# GrovePi__2_2.net
KiCad netlist of a schematic drawn in EAGLE
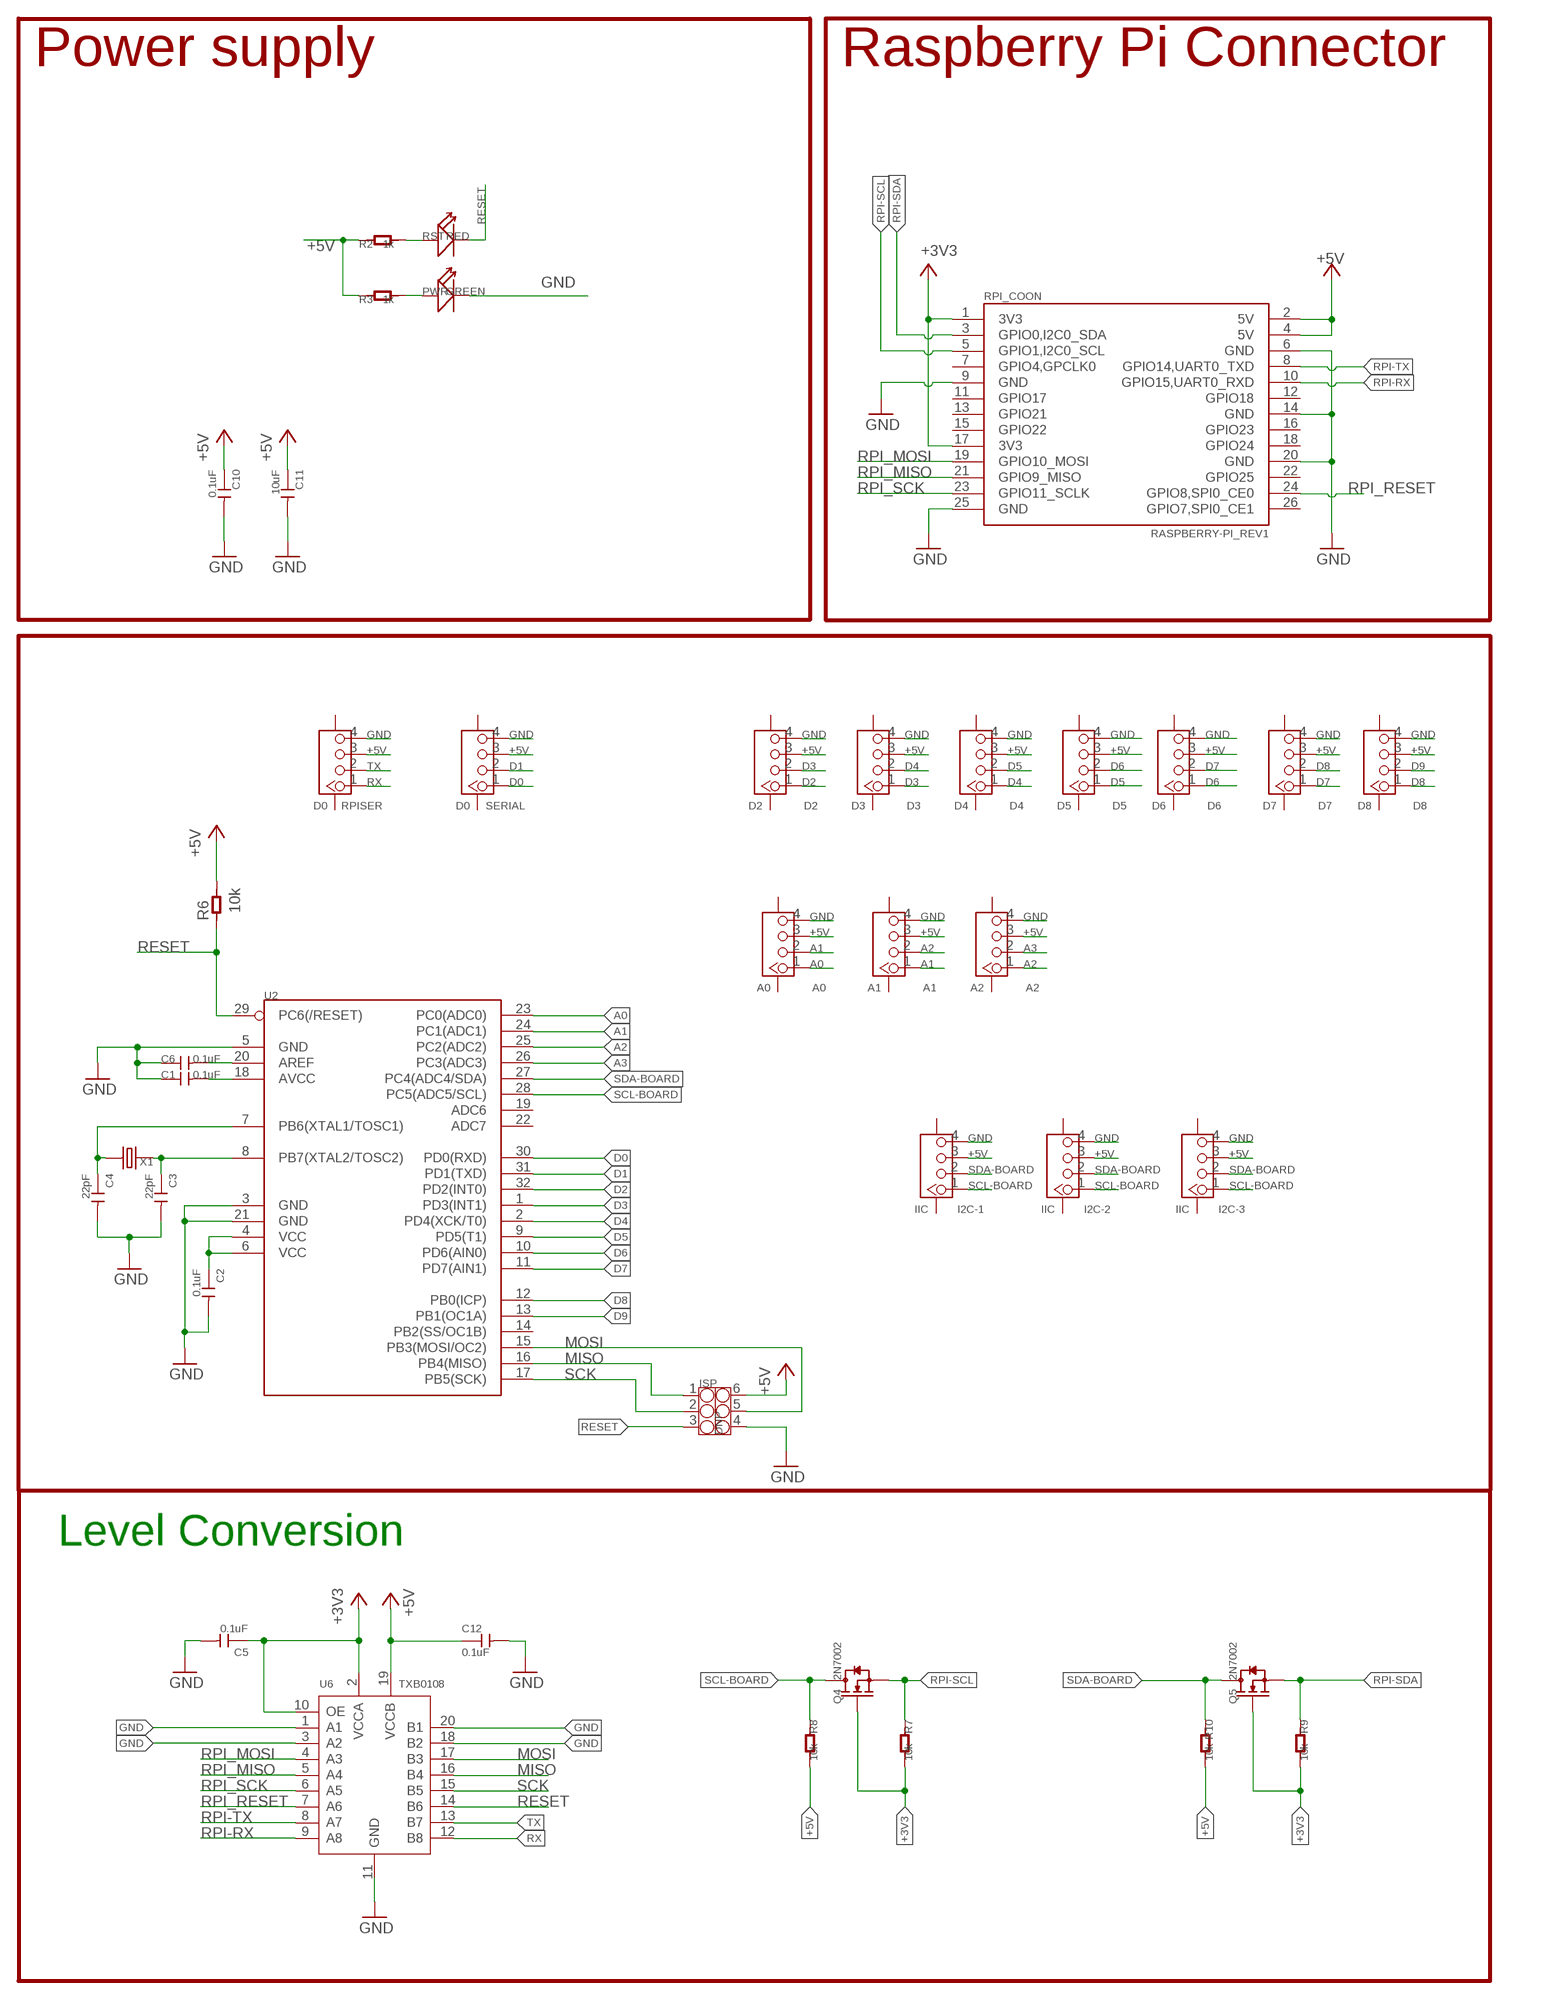
[diagram p0: schematic, sheet 1]

(export (version "E")
  (design (tool "Eeschema 10.0.6"))
  (components
    (comp (ref "A0")
      (value "A0")
      (footprint "eagle-import:4P-SMD-2.0-90D")
      (libsource (lib "eagle-import") (part "GROVE-CONNECTOR-SMD'90D'"))
    )
    (comp (ref "A1")
      (value "A1")
      (footprint "eagle-import:4P-SMD-2.0-90D")
      (libsource (lib "eagle-import") (part "GROVE-CONNECTOR-SMD'90D'"))
    )
    (comp (ref "A2")
      (value "A2")
      (footprint "eagle-import:4P-SMD-2.0-90D")
      (libsource (lib "eagle-import") (part "GROVE-CONNECTOR-SMD'90D'"))
    )
    (comp (ref "C1")
      (value "0.1uF")
      (footprint "eagle-import:C0603")
      (libsource (lib "eagle-import") (part "CAP-0603"))
    )
    (comp (ref "C2")
      (value "0.1uF")
      (footprint "eagle-import:C0603")
      (libsource (lib "eagle-import") (part "CAP-0603"))
    )
    (comp (ref "C3")
      (value "22pF")
      (footprint "eagle-import:C0603")
      (libsource (lib "eagle-import") (part "CAP-0603"))
    )
    (comp (ref "C4")
      (value "22pF")
      (footprint "eagle-import:C0603")
      (libsource (lib "eagle-import") (part "CAP-0603"))
    )
    (comp (ref "C5")
      (value "0.1uF")
      (footprint "eagle-import:C0603")
      (libsource (lib "eagle-import") (part "CAP-0603"))
    )
    (comp (ref "C6")
      (value "0.1uF")
      (footprint "eagle-import:C0603")
      (libsource (lib "eagle-import") (part "CAP-0603"))
    )
    (comp (ref "C10")
      (value "0.1uF")
      (footprint "eagle-import:C0603")
      (libsource (lib "eagle-import") (part "CAP-0603"))
    )
    (comp (ref "C11")
      (value "10uF")
      (footprint "eagle-import:C0805")
      (libsource (lib "eagle-import") (part "CAP-0805"))
    )
    (comp (ref "C12")
      (value "0.1uF")
      (footprint "eagle-import:C0603")
      (libsource (lib "eagle-import") (part "CAP-0603"))
    )
    (comp (ref "D2")
      (value "D2")
      (footprint "eagle-import:4P-SMD-2.0-90D")
      (libsource (lib "eagle-import") (part "GROVE-CONNECTOR-SMD'90D'"))
    )
    (comp (ref "D3")
      (value "D3")
      (footprint "eagle-import:4P-SMD-2.0-90D")
      (libsource (lib "eagle-import") (part "GROVE-CONNECTOR-SMD'90D'"))
    )
    (comp (ref "D4")
      (value "D4")
      (footprint "eagle-import:4P-SMD-2.0-90D")
      (libsource (lib "eagle-import") (part "GROVE-CONNECTOR-SMD'90D'"))
    )
    (comp (ref "D5")
      (value "D5")
      (footprint "eagle-import:4P-SMD-2.0")
      (libsource (lib "eagle-import") (part "GROVE-CONNECTOR-SMD'DD'"))
    )
    (comp (ref "D6")
      (value "D6")
      (footprint "eagle-import:4P-SMD-2.0")
      (libsource (lib "eagle-import") (part "GROVE-CONNECTOR-SMD'DD'"))
    )
    (comp (ref "D7")
      (value "D7")
      (footprint "eagle-import:4P-SMD-2.0-90D")
      (libsource (lib "eagle-import") (part "GROVE-CONNECTOR-SMD'90D'"))
    )
    (comp (ref "D8")
      (value "D8")
      (footprint "eagle-import:4P-SMD-2.0-90D")
      (libsource (lib "eagle-import") (part "GROVE-CONNECTOR-SMD'90D'"))
    )
    (comp (ref "I2C-1")
      (value "IIC")
      (footprint "eagle-import:4P-SMD-2.0-90D")
      (libsource (lib "eagle-import") (part "GROVE-CONNECTOR-SMD'90D'"))
    )
    (comp (ref "I2C-2")
      (value "IIC")
      (footprint "eagle-import:4P-SMD-2.0-90D")
      (libsource (lib "eagle-import") (part "GROVE-CONNECTOR-SMD'90D'"))
    )
    (comp (ref "I2C-3")
      (value "IIC")
      (footprint "eagle-import:4P-SMD-2.0-90D")
      (libsource (lib "eagle-import") (part "GROVE-CONNECTOR-SMD'90D'"))
    )
    (comp (ref "ISP")
      (value "DNP")
      (footprint "eagle-import:2X3P-2.54-2.54-11.6-3.0-BLACK-MALE")
      (libsource (lib "eagle-import") (part "CONNECTOR-HEADER-2X3P-3460180P1"))
    )
    (comp (ref "PWR")
      (value "GREEN")
      (footprint "eagle-import:LED0603")
      (libsource (lib "eagle-import") (part "LED"))
    )
    (comp (ref "Q4")
      (value "2N7002")
      (footprint "eagle-import:SOT23")
      (libsource (lib "eagle-import") (part "MOSFET-N-''"))
    )
    (comp (ref "Q5")
      (value "2N7002")
      (footprint "eagle-import:SOT23")
      (libsource (lib "eagle-import") (part "MOSFET-N-''"))
    )
    (comp (ref "R2")
      (value "1k")
      (footprint "eagle-import:R0603")
      (libsource (lib "eagle-import") (part "R-0603"))
    )
    (comp (ref "R3")
      (value "1k")
      (footprint "eagle-import:R0603")
      (libsource (lib "eagle-import") (part "R-0603"))
    )
    (comp (ref "R6")
      (value "10k")
      (footprint "eagle-import:R0603")
      (libsource (lib "eagle-import") (part "R-0603"))
    )
    (comp (ref "R7")
      (value "10k")
      (footprint "eagle-import:R0603")
      (libsource (lib "eagle-import") (part "R-0603"))
    )
    (comp (ref "R8")
      (value "10k")
      (footprint "eagle-import:R0603")
      (libsource (lib "eagle-import") (part "R-0603"))
    )
    (comp (ref "R9")
      (value "10k")
      (footprint "eagle-import:R0603")
      (libsource (lib "eagle-import") (part "R-0603"))
    )
    (comp (ref "R10")
      (value "10k")
      (footprint "eagle-import:R0603")
      (libsource (lib "eagle-import") (part "R-0603"))
    )
    (comp (ref "RPISER")
      (value "D0")
      (footprint "eagle-import:4P-SMD-2.0-90D")
      (libsource (lib "eagle-import") (part "GROVE-CONNECTOR-SMD'90D'"))
    )
    (comp (ref "RPI_COON")
      (value "RASPBERRY-PI_REV1")
      (footprint "eagle-import:RASPBERRY-PI_REV1")
      (libsource (lib "eagle-import") (part "RASPBERRY-PI_REV1"))
    )
    (comp (ref "RST")
      (value "RED")
      (footprint "eagle-import:LED0603")
      (libsource (lib "eagle-import") (part "LED"))
    )
    (comp (ref "SERIAL")
      (value "D0")
      (footprint "eagle-import:4P-SMD-2.0-90D")
      (libsource (lib "eagle-import") (part "GROVE-CONNECTOR-SMD'90D'"))
    )
    (comp (ref "U2")
      (value "ATMEGA328P-AU-1030060P1")
      (footprint "eagle-import:TQFP32")
      (libsource (lib "eagle-import") (part "ATMEGA328P-AU-1030060P1"))
    )
    (comp (ref "U6")
      (value "TXB0108")
      (footprint "eagle-import:TSSOP20")
      (libsource (lib "eagle-import") (part "TXS0108E"))
    )
    (comp (ref "X1")
      (value "CRYSTAL")
      (footprint "eagle-import:HC49US")
      (libsource (lib "eagle-import") (part "CRYSTAL"))
    )
  )
  (nets
    (net (code "1") (name "+3V3") (class "Default")
      (node (ref "C5") (pin "1") (pinfunction "1_1") (pintype "passive"))
      (node (ref "Q4") (pin "1") (pinfunction "G_1") (pintype "passive"))
      (node (ref "Q5") (pin "1") (pinfunction "G_1") (pintype "passive"))
      (node (ref "R7") (pin "2") (pinfunction "2_2") (pintype "bidirectional"))
      (node (ref "R9") (pin "2") (pinfunction "2_2") (pintype "bidirectional"))
      (node (ref "RPI_COON") (pin "1") (pinfunction "3V3_1") (pintype "bidirectional"))
      (node (ref "RPI_COON") (pin "17") (pinfunction "3V3_17") (pintype "bidirectional"))
      (node (ref "U6") (pin "10") (pinfunction "OE_10") (pintype "bidirectional"))
      (node (ref "U6") (pin "2") (pinfunction "VCCA_2") (pintype "bidirectional"))
    )
    (net (code "2") (name "+5V") (class "Default")
      (node (ref "A0") (pin "3") (pinfunction "3_3") (pintype "bidirectional"))
      (node (ref "A1") (pin "3") (pinfunction "3_3") (pintype "bidirectional"))
      (node (ref "A2") (pin "3") (pinfunction "3_3") (pintype "bidirectional"))
      (node (ref "C10") (pin "1") (pinfunction "1_1") (pintype "passive"))
      (node (ref "C11") (pin "1") (pinfunction "1_1") (pintype "passive"))
      (node (ref "C12") (pin "1") (pinfunction "1_1") (pintype "passive"))
      (node (ref "D2") (pin "3") (pinfunction "3_3") (pintype "bidirectional"))
      (node (ref "D3") (pin "3") (pinfunction "3_3") (pintype "bidirectional"))
      (node (ref "D4") (pin "3") (pinfunction "3_3") (pintype "bidirectional"))
      (node (ref "D5") (pin "3") (pinfunction "3_3") (pintype "bidirectional"))
      (node (ref "D6") (pin "3") (pinfunction "3_3") (pintype "bidirectional"))
      (node (ref "D7") (pin "3") (pinfunction "3_3") (pintype "bidirectional"))
      (node (ref "D8") (pin "3") (pinfunction "3_3") (pintype "bidirectional"))
      (node (ref "I2C-1") (pin "3") (pinfunction "3_3") (pintype "bidirectional"))
      (node (ref "I2C-2") (pin "3") (pinfunction "3_3") (pintype "bidirectional"))
      (node (ref "I2C-3") (pin "3") (pinfunction "3_3") (pintype "bidirectional"))
      (node (ref "ISP") (pin "6") (pinfunction "6_6") (pintype "bidirectional"))
      (node (ref "R10") (pin "2") (pinfunction "2_2") (pintype "bidirectional"))
      (node (ref "R2") (pin "1") (pinfunction "1_1") (pintype "bidirectional"))
      (node (ref "R3") (pin "1") (pinfunction "1_1") (pintype "bidirectional"))
      (node (ref "R6") (pin "2") (pinfunction "2_2") (pintype "bidirectional"))
      (node (ref "R8") (pin "2") (pinfunction "2_2") (pintype "bidirectional"))
      (node (ref "RPISER") (pin "3") (pinfunction "3_3") (pintype "bidirectional"))
      (node (ref "RPI_COON") (pin "2") (pinfunction "5V_2") (pintype "bidirectional"))
      (node (ref "RPI_COON") (pin "4") (pinfunction "5V_4") (pintype "bidirectional"))
      (node (ref "SERIAL") (pin "3") (pinfunction "3_3") (pintype "bidirectional"))
      (node (ref "U6") (pin "19") (pinfunction "VCCB_19") (pintype "bidirectional"))
    )
    (net (code "3") (name "/MISO") (class "Default")
      (node (ref "ISP") (pin "1") (pinfunction "1_1") (pintype "bidirectional"))
      (node (ref "U2") (pin "16") (pinfunction "PB4(MISO)_16") (pintype "bidirectional"))
      (node (ref "U6") (pin "16") (pinfunction "B4_16") (pintype "bidirectional"))
    )
    (net (code "4") (name "/MOSI") (class "Default")
      (node (ref "ISP") (pin "5") (pinfunction "5_5") (pintype "bidirectional"))
      (node (ref "U2") (pin "15") (pinfunction "PB3(MOSI/OC2)_15") (pintype "bidirectional"))
      (node (ref "U6") (pin "17") (pinfunction "B3_17") (pintype "bidirectional"))
    )
    (net (code "5") (name "/RPI_MISO") (class "Default")
      (node (ref "RPI_COON") (pin "21") (pinfunction "GPIO9_MISO_21") (pintype "bidirectional"))
      (node (ref "U6") (pin "5") (pinfunction "A4_5") (pintype "bidirectional"))
    )
    (net (code "6") (name "/RPI_MOSI") (class "Default")
      (node (ref "RPI_COON") (pin "19") (pinfunction "GPIO10_MOSI_19") (pintype "bidirectional"))
      (node (ref "U6") (pin "4") (pinfunction "A3_4") (pintype "bidirectional"))
    )
    (net (code "7") (name "/RPI_RESET") (class "Default")
      (node (ref "RPI_COON") (pin "24") (pinfunction "GPIO8,SPI0_CE0_24") (pintype "bidirectional"))
      (node (ref "U6") (pin "7") (pinfunction "A6_7") (pintype "bidirectional"))
    )
    (net (code "8") (name "/RPI_SCK") (class "Default")
      (node (ref "RPI_COON") (pin "23") (pinfunction "GPIO11_SCLK_23") (pintype "bidirectional"))
      (node (ref "U6") (pin "6") (pinfunction "A5_6") (pintype "bidirectional"))
    )
    (net (code "9") (name "/SCK") (class "Default")
      (node (ref "ISP") (pin "2") (pinfunction "2_2") (pintype "bidirectional"))
      (node (ref "U2") (pin "17") (pinfunction "PB5(SCK)_17") (pintype "bidirectional"))
      (node (ref "U6") (pin "15") (pinfunction "B5_15") (pintype "bidirectional"))
    )
    (net (code "10") (name "A0") (class "Default")
      (node (ref "A0") (pin "1") (pinfunction "1_1") (pintype "bidirectional"))
      (node (ref "U2") (pin "23") (pinfunction "PC0(ADC0)_23") (pintype "bidirectional"))
    )
    (net (code "11") (name "A1") (class "Default")
      (node (ref "A0") (pin "2") (pinfunction "2_2") (pintype "bidirectional"))
      (node (ref "A1") (pin "1") (pinfunction "1_1") (pintype "bidirectional"))
      (node (ref "U2") (pin "24") (pinfunction "PC1(ADC1)_24") (pintype "bidirectional"))
    )
    (net (code "12") (name "A2") (class "Default")
      (node (ref "A1") (pin "2") (pinfunction "2_2") (pintype "bidirectional"))
      (node (ref "A2") (pin "1") (pinfunction "1_1") (pintype "bidirectional"))
      (node (ref "U2") (pin "25") (pinfunction "PC2(ADC2)_25") (pintype "bidirectional"))
    )
    (net (code "13") (name "A3") (class "Default")
      (node (ref "A2") (pin "2") (pinfunction "2_2") (pintype "bidirectional"))
      (node (ref "U2") (pin "26") (pinfunction "PC3(ADC3)_26") (pintype "bidirectional"))
    )
    (net (code "14") (name "D0") (class "Default")
      (node (ref "SERIAL") (pin "1") (pinfunction "1_1") (pintype "bidirectional"))
      (node (ref "U2") (pin "30") (pinfunction "PD0(RXD)_30") (pintype "bidirectional"))
    )
    (net (code "15") (name "D1") (class "Default")
      (node (ref "SERIAL") (pin "2") (pinfunction "2_2") (pintype "bidirectional"))
      (node (ref "U2") (pin "31") (pinfunction "PD1(TXD)_31") (pintype "bidirectional"))
    )
    (net (code "16") (name "D2") (class "Default")
      (node (ref "D2") (pin "1") (pinfunction "1_1") (pintype "bidirectional"))
      (node (ref "U2") (pin "32") (pinfunction "PD2(INT0)_32") (pintype "bidirectional"))
    )
    (net (code "17") (name "D3") (class "Default")
      (node (ref "D2") (pin "2") (pinfunction "2_2") (pintype "bidirectional"))
      (node (ref "D3") (pin "1") (pinfunction "1_1") (pintype "bidirectional"))
      (node (ref "U2") (pin "1") (pinfunction "PD3(INT1)_1") (pintype "bidirectional"))
    )
    (net (code "18") (name "D4") (class "Default")
      (node (ref "D3") (pin "2") (pinfunction "2_2") (pintype "bidirectional"))
      (node (ref "D4") (pin "1") (pinfunction "1_1") (pintype "bidirectional"))
      (node (ref "U2") (pin "2") (pinfunction "PD4(XCK/T0)_2") (pintype "bidirectional"))
    )
    (net (code "19") (name "D5") (class "Default")
      (node (ref "D4") (pin "2") (pinfunction "2_2") (pintype "bidirectional"))
      (node (ref "D5") (pin "1") (pinfunction "1_1") (pintype "bidirectional"))
      (node (ref "U2") (pin "9") (pinfunction "PD5(T1)_9") (pintype "bidirectional"))
    )
    (net (code "20") (name "D6") (class "Default")
      (node (ref "D5") (pin "2") (pinfunction "2_2") (pintype "bidirectional"))
      (node (ref "D6") (pin "1") (pinfunction "1_1") (pintype "bidirectional"))
      (node (ref "U2") (pin "10") (pinfunction "PD6(AIN0)_10") (pintype "bidirectional"))
    )
    (net (code "21") (name "D7") (class "Default")
      (node (ref "D6") (pin "2") (pinfunction "2_2") (pintype "bidirectional"))
      (node (ref "D7") (pin "1") (pinfunction "1_1") (pintype "bidirectional"))
      (node (ref "U2") (pin "11") (pinfunction "PD7(AIN1)_11") (pintype "bidirectional"))
    )
    (net (code "22") (name "D8") (class "Default")
      (node (ref "D7") (pin "2") (pinfunction "2_2") (pintype "bidirectional"))
      (node (ref "D8") (pin "1") (pinfunction "1_1") (pintype "bidirectional"))
      (node (ref "U2") (pin "12") (pinfunction "PB0(ICP)_12") (pintype "bidirectional"))
    )
    (net (code "23") (name "D9") (class "Default")
      (node (ref "D8") (pin "2") (pinfunction "2_2") (pintype "bidirectional"))
      (node (ref "U2") (pin "13") (pinfunction "PB1(OC1A)_13") (pintype "bidirectional"))
    )
    (net (code "24") (name "GND") (class "Default")
      (node (ref "A0") (pin "4") (pinfunction "4_4") (pintype "bidirectional"))
      (node (ref "A1") (pin "4") (pinfunction "4_4") (pintype "bidirectional"))
      (node (ref "A2") (pin "4") (pinfunction "4_4") (pintype "bidirectional"))
      (node (ref "C1") (pin "1") (pinfunction "1_1") (pintype "passive"))
      (node (ref "C10") (pin "2") (pinfunction "2_2") (pintype "passive"))
      (node (ref "C11") (pin "2") (pinfunction "2_2") (pintype "passive"))
      (node (ref "C12") (pin "2") (pinfunction "2_2") (pintype "passive"))
      (node (ref "C2") (pin "2") (pinfunction "2_2") (pintype "passive"))
      (node (ref "C3") (pin "2") (pinfunction "2_2") (pintype "passive"))
      (node (ref "C4") (pin "2") (pinfunction "2_2") (pintype "passive"))
      (node (ref "C5") (pin "2") (pinfunction "2_2") (pintype "passive"))
      (node (ref "C6") (pin "1") (pinfunction "1_1") (pintype "passive"))
      (node (ref "D2") (pin "4") (pinfunction "4_4") (pintype "bidirectional"))
      (node (ref "D3") (pin "4") (pinfunction "4_4") (pintype "bidirectional"))
      (node (ref "D4") (pin "4") (pinfunction "4_4") (pintype "bidirectional"))
      (node (ref "D5") (pin "4") (pinfunction "4_4") (pintype "bidirectional"))
      (node (ref "D6") (pin "4") (pinfunction "4_4") (pintype "bidirectional"))
      (node (ref "D7") (pin "4") (pinfunction "4_4") (pintype "bidirectional"))
      (node (ref "D8") (pin "4") (pinfunction "4_4") (pintype "bidirectional"))
      (node (ref "I2C-1") (pin "4") (pinfunction "4_4") (pintype "bidirectional"))
      (node (ref "I2C-2") (pin "4") (pinfunction "4_4") (pintype "bidirectional"))
      (node (ref "I2C-3") (pin "4") (pinfunction "4_4") (pintype "bidirectional"))
      (node (ref "ISP") (pin "4") (pinfunction "4_4") (pintype "bidirectional"))
      (node (ref "PWR") (pin "-") (pinfunction "-_-") (pintype "passive"))
      (node (ref "RPISER") (pin "4") (pinfunction "4_4") (pintype "bidirectional"))
      (node (ref "RPI_COON") (pin "14") (pinfunction "GND_14") (pintype "bidirectional"))
      (node (ref "RPI_COON") (pin "20") (pinfunction "GND_20") (pintype "bidirectional"))
      (node (ref "RPI_COON") (pin "25") (pinfunction "GND_25") (pintype "bidirectional"))
      (node (ref "RPI_COON") (pin "6") (pinfunction "GND_6") (pintype "bidirectional"))
      (node (ref "RPI_COON") (pin "9") (pinfunction "GND_9") (pintype "bidirectional"))
      (node (ref "SERIAL") (pin "4") (pinfunction "4_4") (pintype "bidirectional"))
      (node (ref "U2") (pin "21") (pinfunction "GND_21") (pintype "bidirectional"))
      (node (ref "U2") (pin "3") (pinfunction "GND_3") (pintype "bidirectional"))
      (node (ref "U2") (pin "5") (pinfunction "GND_5") (pintype "bidirectional"))
      (node (ref "U6") (pin "1") (pinfunction "A1_1") (pintype "bidirectional"))
      (node (ref "U6") (pin "11") (pinfunction "GND_11") (pintype "bidirectional"))
      (node (ref "U6") (pin "18") (pinfunction "B2_18") (pintype "bidirectional"))
      (node (ref "U6") (pin "20") (pinfunction "B1_20") (pintype "bidirectional"))
      (node (ref "U6") (pin "3") (pinfunction "A2_3") (pintype "bidirectional"))
    )
    (net (code "25") (name "Net-(C2-Pad1)") (class "Default")
      (node (ref "C2") (pin "1") (pinfunction "1_1") (pintype "passive"))
      (node (ref "U2") (pin "4") (pinfunction "VCC_4") (pintype "bidirectional"))
      (node (ref "U2") (pin "6") (pinfunction "VCC_6") (pintype "bidirectional"))
    )
    (net (code "26") (name "Net-(PWR-Pad+)") (class "Default")
      (node (ref "PWR") (pin "+") (pinfunction "+_+") (pintype "passive"))
      (node (ref "R3") (pin "2") (pinfunction "2_2") (pintype "bidirectional"))
    )
    (net (code "27") (name "Net-(R2-Pad2)") (class "Default")
      (node (ref "R2") (pin "2") (pinfunction "2_2") (pintype "bidirectional"))
      (node (ref "RST") (pin "+") (pinfunction "+_+") (pintype "passive"))
    )
    (net (code "28") (name "Net-(U2-AREF)") (class "Default")
      (node (ref "C6") (pin "2") (pinfunction "2_2") (pintype "passive"))
      (node (ref "U2") (pin "20") (pinfunction "AREF_20") (pintype "bidirectional"))
    )
    (net (code "29") (name "Net-(U2-AVCC)") (class "Default")
      (node (ref "C1") (pin "2") (pinfunction "2_2") (pintype "passive"))
      (node (ref "U2") (pin "18") (pinfunction "AVCC_18") (pintype "bidirectional"))
    )
    (net (code "30") (name "Net-(U2-PB6(XTAL1{slash}TOSC1))") (class "Default")
      (node (ref "C4") (pin "1") (pinfunction "1_1") (pintype "passive"))
      (node (ref "U2") (pin "7") (pinfunction "PB6(XTAL1/TOSC1)_7") (pintype "bidirectional"))
      (node (ref "X1") (pin "2") (pinfunction "2_2") (pintype "passive"))
    )
    (net (code "31") (name "Net-(U2-PB7(XTAL2{slash}TOSC2))") (class "Default")
      (node (ref "C3") (pin "1") (pinfunction "1_1") (pintype "passive"))
      (node (ref "U2") (pin "8") (pinfunction "PB7(XTAL2/TOSC2)_8") (pintype "bidirectional"))
      (node (ref "X1") (pin "1") (pinfunction "1_1") (pintype "passive"))
    )
    (net (code "32") (name "RESET") (class "Default")
      (node (ref "ISP") (pin "3") (pinfunction "3_3") (pintype "bidirectional"))
      (node (ref "R6") (pin "1") (pinfunction "1_1") (pintype "bidirectional"))
      (node (ref "RST") (pin "-") (pinfunction "-_-") (pintype "passive"))
      (node (ref "U2") (pin "29") (pinfunction "PC6(/RESET)_29") (pintype "bidirectional"))
      (node (ref "U6") (pin "14") (pinfunction "B6_14") (pintype "bidirectional"))
    )
    (net (code "33") (name "RPI-RX") (class "Default")
      (node (ref "RPI_COON") (pin "10") (pinfunction "GPIO15,UART0_RXD_10") (pintype "bidirectional"))
      (node (ref "U6") (pin "9") (pinfunction "A8_9") (pintype "bidirectional"))
    )
    (net (code "34") (name "RPI-SCL") (class "Default")
      (node (ref "Q4") (pin "2") (pinfunction "S_2") (pintype "passive"))
      (node (ref "R7") (pin "1") (pinfunction "1_1") (pintype "bidirectional"))
      (node (ref "RPI_COON") (pin "5") (pinfunction "GPIO1,I2C0_SCL_5") (pintype "bidirectional"))
    )
    (net (code "35") (name "RPI-SDA") (class "Default")
      (node (ref "Q5") (pin "2") (pinfunction "S_2") (pintype "passive"))
      (node (ref "R9") (pin "1") (pinfunction "1_1") (pintype "bidirectional"))
      (node (ref "RPI_COON") (pin "3") (pinfunction "GPIO0,I2C0_SDA_3") (pintype "bidirectional"))
    )
    (net (code "36") (name "RPI-TX") (class "Default")
      (node (ref "RPI_COON") (pin "8") (pinfunction "GPIO14,UART0_TXD_8") (pintype "bidirectional"))
      (node (ref "U6") (pin "8") (pinfunction "A7_8") (pintype "bidirectional"))
    )
    (net (code "37") (name "RX") (class "Default")
      (node (ref "RPISER") (pin "1") (pinfunction "1_1") (pintype "bidirectional"))
      (node (ref "U6") (pin "12") (pinfunction "B8_12") (pintype "bidirectional"))
    )
    (net (code "38") (name "SCL-BOARD") (class "Default")
      (node (ref "I2C-1") (pin "1") (pinfunction "1_1") (pintype "bidirectional"))
      (node (ref "I2C-2") (pin "1") (pinfunction "1_1") (pintype "bidirectional"))
      (node (ref "I2C-3") (pin "1") (pinfunction "1_1") (pintype "bidirectional"))
      (node (ref "Q4") (pin "3") (pinfunction "D_3") (pintype "passive"))
      (node (ref "R8") (pin "1") (pinfunction "1_1") (pintype "bidirectional"))
      (node (ref "U2") (pin "28") (pinfunction "PC5(ADC5/SCL)_28") (pintype "bidirectional"))
    )
    (net (code "39") (name "SDA-BOARD") (class "Default")
      (node (ref "I2C-1") (pin "2") (pinfunction "2_2") (pintype "bidirectional"))
      (node (ref "I2C-2") (pin "2") (pinfunction "2_2") (pintype "bidirectional"))
      (node (ref "I2C-3") (pin "2") (pinfunction "2_2") (pintype "bidirectional"))
      (node (ref "Q5") (pin "3") (pinfunction "D_3") (pintype "passive"))
      (node (ref "R10") (pin "1") (pinfunction "1_1") (pintype "bidirectional"))
      (node (ref "U2") (pin "27") (pinfunction "PC4(ADC4/SDA)_27") (pintype "bidirectional"))
    )
    (net (code "40") (name "TX") (class "Default")
      (node (ref "RPISER") (pin "2") (pinfunction "2_2") (pintype "bidirectional"))
      (node (ref "U6") (pin "13") (pinfunction "B7_13") (pintype "bidirectional"))
    )
    (net (code "41") (name "unconnected-(A0-PadSS1)") (class "Default")
      (node (ref "A0") (pin "SS1") (pinfunction "SS1_SS1") (pintype "bidirectional"))
    )
    (net (code "42") (name "unconnected-(A0-PadSS2)") (class "Default")
      (node (ref "A0") (pin "SS2") (pinfunction "SS2_SS2") (pintype "bidirectional"))
    )
    (net (code "43") (name "unconnected-(A1-PadSS1)") (class "Default")
      (node (ref "A1") (pin "SS1") (pinfunction "SS1_SS1") (pintype "bidirectional"))
    )
    (net (code "44") (name "unconnected-(A1-PadSS2)") (class "Default")
      (node (ref "A1") (pin "SS2") (pinfunction "SS2_SS2") (pintype "bidirectional"))
    )
    (net (code "45") (name "unconnected-(A2-PadSS1)") (class "Default")
      (node (ref "A2") (pin "SS1") (pinfunction "SS1_SS1") (pintype "bidirectional"))
    )
    (net (code "46") (name "unconnected-(A2-PadSS2)") (class "Default")
      (node (ref "A2") (pin "SS2") (pinfunction "SS2_SS2") (pintype "bidirectional"))
    )
    (net (code "47") (name "unconnected-(D2-PadSS1)") (class "Default")
      (node (ref "D2") (pin "SS1") (pinfunction "SS1_SS1") (pintype "bidirectional"))
    )
    (net (code "48") (name "unconnected-(D2-PadSS2)") (class "Default")
      (node (ref "D2") (pin "SS2") (pinfunction "SS2_SS2") (pintype "bidirectional"))
    )
    (net (code "49") (name "unconnected-(D3-PadSS1)") (class "Default")
      (node (ref "D3") (pin "SS1") (pinfunction "SS1_SS1") (pintype "bidirectional"))
    )
    (net (code "50") (name "unconnected-(D3-PadSS2)") (class "Default")
      (node (ref "D3") (pin "SS2") (pinfunction "SS2_SS2") (pintype "bidirectional"))
    )
    (net (code "51") (name "unconnected-(D4-PadSS1)") (class "Default")
      (node (ref "D4") (pin "SS1") (pinfunction "SS1_SS1") (pintype "bidirectional"))
    )
    (net (code "52") (name "unconnected-(D4-PadSS2)") (class "Default")
      (node (ref "D4") (pin "SS2") (pinfunction "SS2_SS2") (pintype "bidirectional"))
    )
    (net (code "53") (name "unconnected-(D5-PadSS1)") (class "Default")
      (node (ref "D5") (pin "SS1") (pinfunction "SS1_SS1") (pintype "bidirectional"))
    )
    (net (code "54") (name "unconnected-(D5-PadSS2)") (class "Default")
      (node (ref "D5") (pin "SS2") (pinfunction "SS2_SS2") (pintype "bidirectional"))
    )
    (net (code "55") (name "unconnected-(D6-PadSS1)") (class "Default")
      (node (ref "D6") (pin "SS1") (pinfunction "SS1_SS1") (pintype "bidirectional"))
    )
    (net (code "56") (name "unconnected-(D6-PadSS2)") (class "Default")
      (node (ref "D6") (pin "SS2") (pinfunction "SS2_SS2") (pintype "bidirectional"))
    )
    (net (code "57") (name "unconnected-(D7-PadSS1)") (class "Default")
      (node (ref "D7") (pin "SS1") (pinfunction "SS1_SS1") (pintype "bidirectional"))
    )
    (net (code "58") (name "unconnected-(D7-PadSS2)") (class "Default")
      (node (ref "D7") (pin "SS2") (pinfunction "SS2_SS2") (pintype "bidirectional"))
    )
    (net (code "59") (name "unconnected-(D8-PadSS1)") (class "Default")
      (node (ref "D8") (pin "SS1") (pinfunction "SS1_SS1") (pintype "bidirectional"))
    )
    (net (code "60") (name "unconnected-(D8-PadSS2)") (class "Default")
      (node (ref "D8") (pin "SS2") (pinfunction "SS2_SS2") (pintype "bidirectional"))
    )
    (net (code "61") (name "unconnected-(I2C-1-PadSS1)") (class "Default")
      (node (ref "I2C-1") (pin "SS1") (pinfunction "SS1_SS1") (pintype "bidirectional"))
    )
    (net (code "62") (name "unconnected-(I2C-1-PadSS2)") (class "Default")
      (node (ref "I2C-1") (pin "SS2") (pinfunction "SS2_SS2") (pintype "bidirectional"))
    )
    (net (code "63") (name "unconnected-(I2C-2-PadSS1)") (class "Default")
      (node (ref "I2C-2") (pin "SS1") (pinfunction "SS1_SS1") (pintype "bidirectional"))
    )
    (net (code "64") (name "unconnected-(I2C-2-PadSS2)") (class "Default")
      (node (ref "I2C-2") (pin "SS2") (pinfunction "SS2_SS2") (pintype "bidirectional"))
    )
    (net (code "65") (name "unconnected-(I2C-3-PadSS1)") (class "Default")
      (node (ref "I2C-3") (pin "SS1") (pinfunction "SS1_SS1") (pintype "bidirectional"))
    )
    (net (code "66") (name "unconnected-(I2C-3-PadSS2)") (class "Default")
      (node (ref "I2C-3") (pin "SS2") (pinfunction "SS2_SS2") (pintype "bidirectional"))
    )
    (net (code "67") (name "unconnected-(RPISER-PadSS1)") (class "Default")
      (node (ref "RPISER") (pin "SS1") (pinfunction "SS1_SS1") (pintype "bidirectional"))
    )
    (net (code "68") (name "unconnected-(RPISER-PadSS2)") (class "Default")
      (node (ref "RPISER") (pin "SS2") (pinfunction "SS2_SS2") (pintype "bidirectional"))
    )
    (net (code "69") (name "unconnected-(RPI_COON-GPIO4,GPCLK0-Pad7)") (class "Default")
      (node (ref "RPI_COON") (pin "7") (pinfunction "GPIO4,GPCLK0_7") (pintype "bidirectional"))
    )
    (net (code "70") (name "unconnected-(RPI_COON-GPIO7,SPI0_CE1-Pad26)") (class "Default")
      (node (ref "RPI_COON") (pin "26") (pinfunction "GPIO7,SPI0_CE1_26") (pintype "bidirectional"))
    )
    (net (code "71") (name "unconnected-(RPI_COON-GPIO17-Pad11)") (class "Default")
      (node (ref "RPI_COON") (pin "11") (pinfunction "GPIO17_11") (pintype "bidirectional"))
    )
    (net (code "72") (name "unconnected-(RPI_COON-GPIO18-Pad12)") (class "Default")
      (node (ref "RPI_COON") (pin "12") (pinfunction "GPIO18_12") (pintype "bidirectional"))
    )
    (net (code "73") (name "unconnected-(RPI_COON-GPIO21-Pad13)") (class "Default")
      (node (ref "RPI_COON") (pin "13") (pinfunction "GPIO21_13") (pintype "bidirectional"))
    )
    (net (code "74") (name "unconnected-(RPI_COON-GPIO22-Pad15)") (class "Default")
      (node (ref "RPI_COON") (pin "15") (pinfunction "GPIO22_15") (pintype "bidirectional"))
    )
    (net (code "75") (name "unconnected-(RPI_COON-GPIO23-Pad16)") (class "Default")
      (node (ref "RPI_COON") (pin "16") (pinfunction "GPIO23_16") (pintype "bidirectional"))
    )
    (net (code "76") (name "unconnected-(RPI_COON-GPIO24-Pad18)") (class "Default")
      (node (ref "RPI_COON") (pin "18") (pinfunction "GPIO24_18") (pintype "bidirectional"))
    )
    (net (code "77") (name "unconnected-(RPI_COON-GPIO25-Pad22)") (class "Default")
      (node (ref "RPI_COON") (pin "22") (pinfunction "GPIO25_22") (pintype "bidirectional"))
    )
    (net (code "78") (name "unconnected-(SERIAL-PadSS1)") (class "Default")
      (node (ref "SERIAL") (pin "SS1") (pinfunction "SS1_SS1") (pintype "bidirectional"))
    )
    (net (code "79") (name "unconnected-(SERIAL-PadSS2)") (class "Default")
      (node (ref "SERIAL") (pin "SS2") (pinfunction "SS2_SS2") (pintype "bidirectional"))
    )
    (net (code "80") (name "unconnected-(U2-ADC6-Pad19)") (class "Default")
      (node (ref "U2") (pin "19") (pinfunction "ADC6_19") (pintype "bidirectional"))
    )
    (net (code "81") (name "unconnected-(U2-ADC7-Pad22)") (class "Default")
      (node (ref "U2") (pin "22") (pinfunction "ADC7_22") (pintype "bidirectional"))
    )
    (net (code "82") (name "unconnected-(U2-PB2(SS{slash}OC1B)-Pad14)") (class "Default")
      (node (ref "U2") (pin "14") (pinfunction "PB2(SS/OC1B)_14") (pintype "bidirectional"))
    )
  )
)
